# ColorOrgan_LEDs.net
KiCad netlist of a schematic drawn in Altium Designer
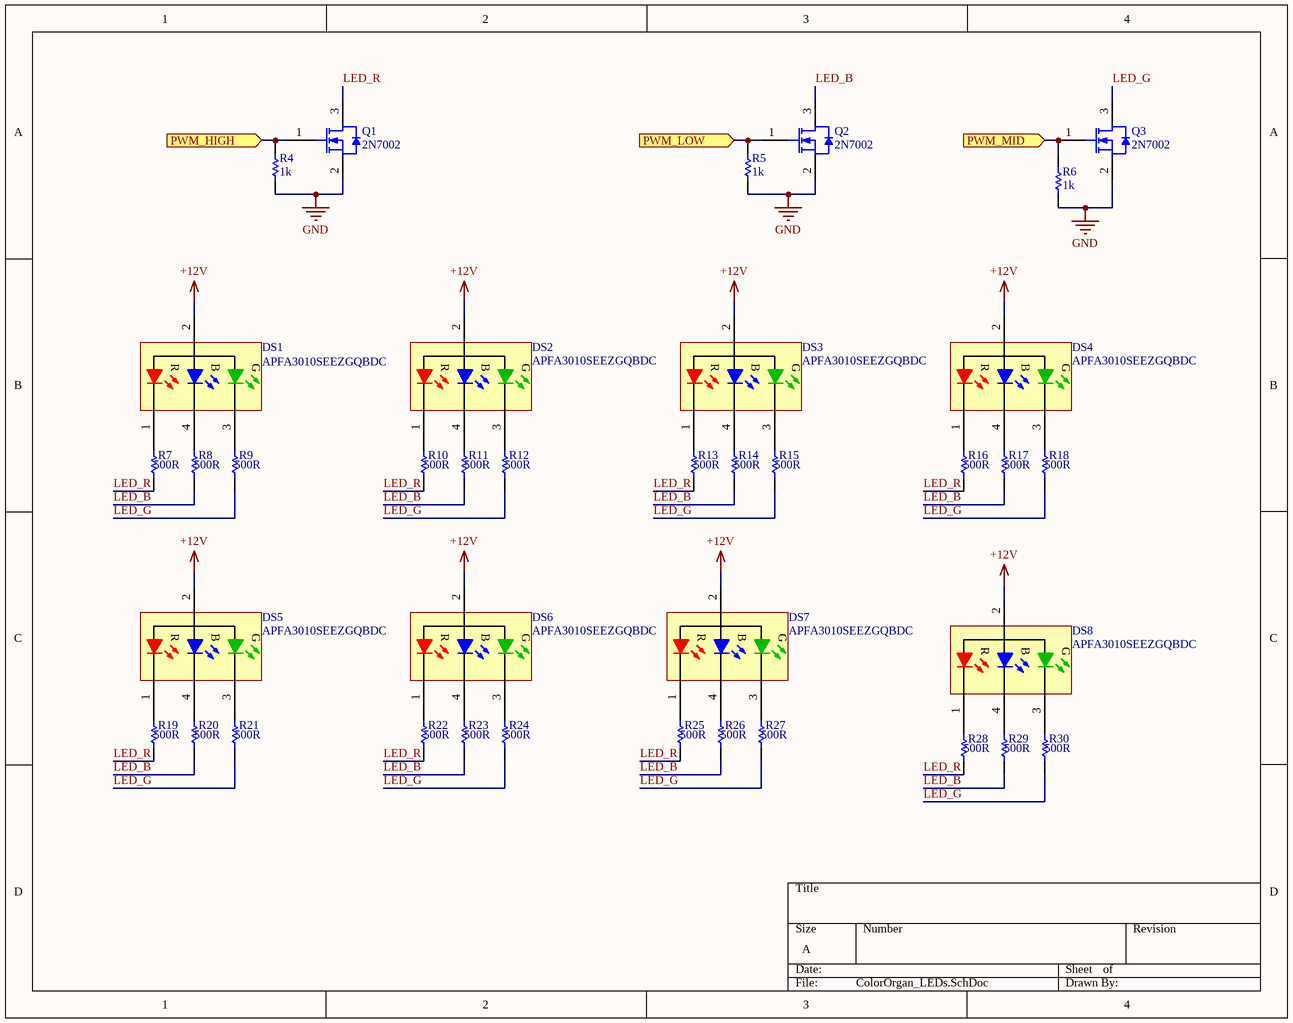
[diagram p0: ColorOrgan_LEDs.SchDoc]

(export (version "E")
  (design (tool "Eeschema 10.0.6"))
  (components
    (comp (ref "DS1")
      (value "APFA3010SEEZGQBDC")
      (footprint "KING-APFA3010SEEZGQBDC-4_V")
      (description "Right Angle SMD Chip LED Lamp, -40 to 85 degC, 4-Pin SMD, RoHS, Reel")
      (fields (field (name "MANUFACTURER") "Kingbright"))
      (libsource (lib "Altium Content Vault") (part "KING-LED_RGB_R1A2G3B4-4"))
    )
    (comp (ref "DS2")
      (value "APFA3010SEEZGQBDC")
      (footprint "KING-APFA3010SEEZGQBDC-4_V")
      (description "Right Angle SMD Chip LED Lamp, -40 to 85 degC, 4-Pin SMD, RoHS, Reel")
      (fields (field (name "MANUFACTURER") "Kingbright"))
      (libsource (lib "Altium Content Vault") (part "KING-LED_RGB_R1A2G3B4-4"))
    )
    (comp (ref "DS3")
      (value "APFA3010SEEZGQBDC")
      (footprint "KING-APFA3010SEEZGQBDC-4_V")
      (description "Right Angle SMD Chip LED Lamp, -40 to 85 degC, 4-Pin SMD, RoHS, Reel")
      (fields (field (name "MANUFACTURER") "Kingbright"))
      (libsource (lib "Altium Content Vault") (part "KING-LED_RGB_R1A2G3B4-4"))
    )
    (comp (ref "DS4")
      (value "APFA3010SEEZGQBDC")
      (footprint "KING-APFA3010SEEZGQBDC-4_V")
      (description "Right Angle SMD Chip LED Lamp, -40 to 85 degC, 4-Pin SMD, RoHS, Reel")
      (fields (field (name "MANUFACTURER") "Kingbright"))
      (libsource (lib "Altium Content Vault") (part "KING-LED_RGB_R1A2G3B4-4"))
    )
    (comp (ref "DS5")
      (value "APFA3010SEEZGQBDC")
      (footprint "KING-APFA3010SEEZGQBDC-4_V")
      (description "Right Angle SMD Chip LED Lamp, -40 to 85 degC, 4-Pin SMD, RoHS, Reel")
      (fields (field (name "MANUFACTURER") "Kingbright"))
      (libsource (lib "Altium Content Vault") (part "KING-LED_RGB_R1A2G3B4-4"))
    )
    (comp (ref "DS6")
      (value "APFA3010SEEZGQBDC")
      (footprint "KING-APFA3010SEEZGQBDC-4_V")
      (description "Right Angle SMD Chip LED Lamp, -40 to 85 degC, 4-Pin SMD, RoHS, Reel")
      (fields (field (name "MANUFACTURER") "Kingbright"))
      (libsource (lib "Altium Content Vault") (part "KING-LED_RGB_R1A2G3B4-4"))
    )
    (comp (ref "DS7")
      (value "APFA3010SEEZGQBDC")
      (footprint "KING-APFA3010SEEZGQBDC-4_V")
      (description "Right Angle SMD Chip LED Lamp, -40 to 85 degC, 4-Pin SMD, RoHS, Reel")
      (fields (field (name "MANUFACTURER") "Kingbright"))
      (libsource (lib "Altium Content Vault") (part "KING-LED_RGB_R1A2G3B4-4"))
    )
    (comp (ref "DS8")
      (value "APFA3010SEEZGQBDC")
      (footprint "KING-APFA3010SEEZGQBDC-4_V")
      (description "Right Angle SMD Chip LED Lamp, -40 to 85 degC, 4-Pin SMD, RoHS, Reel")
      (fields (field (name "MANUFACTURER") "Kingbright"))
      (libsource (lib "Altium Content Vault") (part "KING-LED_RGB_R1A2G3B4-4"))
    )
    (comp (ref "Q1")
      (value "2N7002")
      (footprint "STM-SOT-23-3_V")
      (description "N-channel 60 V, 1.8 Ohm, 0.35 A STripFET(TM) II Power MOSFET, SOT23")
      (fields (field (name "MANUFACTURER") "STMicroelectronics"))
      (libsource (lib "Altium Content Vault") (part "STM-NEMOS-G1S2D3-3"))
    )
    (comp (ref "Q2")
      (value "2N7002")
      (footprint "STM-SOT-23-3_V")
      (description "N-channel 60 V, 1.8 Ohm, 0.35 A STripFET(TM) II Power MOSFET, SOT23")
      (fields (field (name "MANUFACTURER") "STMicroelectronics"))
      (libsource (lib "Altium Content Vault") (part "STM-NEMOS-G1S2D3-3"))
    )
    (comp (ref "Q3")
      (value "2N7002")
      (footprint "STM-SOT-23-3_V")
      (description "N-channel 60 V, 1.8 Ohm, 0.35 A STripFET(TM) II Power MOSFET, SOT23")
      (fields (field (name "MANUFACTURER") "STMicroelectronics"))
      (libsource (lib "Altium Content Vault") (part "STM-NEMOS-G1S2D3-3"))
    )
    (comp (ref "R4")
      (value "1k")
      (footprint "RESC0805(2012)_L")
      (description "0805 (2012 Metric) Chip Resistor")
      (libsource (lib "Altium Content Vault") (part "RES_3"))
    )
    (comp (ref "R5")
      (value "1k")
      (footprint "RESC0805(2012)_L")
      (description "0805 (2012 Metric) Chip Resistor")
      (libsource (lib "Altium Content Vault") (part "RES_3"))
    )
    (comp (ref "R6")
      (value "1k")
      (footprint "RESC0805(2012)_L")
      (description "0805 (2012 Metric) Chip Resistor")
      (libsource (lib "Altium Content Vault") (part "RES_3"))
    )
    (comp (ref "R7")
      (value "500R")
      (footprint "RESC0805(2012)_L")
      (description "0805 (2012 Metric) Chip Resistor")
      (libsource (lib "Altium Content Vault") (part "RES_3"))
    )
    (comp (ref "R8")
      (value "500R")
      (footprint "RESC0805(2012)_L")
      (description "0805 (2012 Metric) Chip Resistor")
      (libsource (lib "Altium Content Vault") (part "RES_3"))
    )
    (comp (ref "R9")
      (value "500R")
      (footprint "RESC0805(2012)_L")
      (description "0805 (2012 Metric) Chip Resistor")
      (libsource (lib "Altium Content Vault") (part "RES_3"))
    )
    (comp (ref "R10")
      (value "500R")
      (footprint "RESC0805(2012)_L")
      (description "0805 (2012 Metric) Chip Resistor")
      (libsource (lib "Altium Content Vault") (part "RES_3"))
    )
    (comp (ref "R11")
      (value "500R")
      (footprint "RESC0805(2012)_L")
      (description "0805 (2012 Metric) Chip Resistor")
      (libsource (lib "Altium Content Vault") (part "RES_3"))
    )
    (comp (ref "R12")
      (value "500R")
      (footprint "RESC0805(2012)_L")
      (description "0805 (2012 Metric) Chip Resistor")
      (libsource (lib "Altium Content Vault") (part "RES_3"))
    )
    (comp (ref "R13")
      (value "500R")
      (footprint "RESC0805(2012)_L")
      (description "0805 (2012 Metric) Chip Resistor")
      (libsource (lib "Altium Content Vault") (part "RES_3"))
    )
    (comp (ref "R14")
      (value "500R")
      (footprint "RESC0805(2012)_L")
      (description "0805 (2012 Metric) Chip Resistor")
      (libsource (lib "Altium Content Vault") (part "RES_3"))
    )
    (comp (ref "R15")
      (value "500R")
      (footprint "RESC0805(2012)_L")
      (description "0805 (2012 Metric) Chip Resistor")
      (libsource (lib "Altium Content Vault") (part "RES_3"))
    )
    (comp (ref "R16")
      (value "500R")
      (footprint "RESC0805(2012)_L")
      (description "0805 (2012 Metric) Chip Resistor")
      (libsource (lib "Altium Content Vault") (part "RES_3"))
    )
    (comp (ref "R17")
      (value "500R")
      (footprint "RESC0805(2012)_L")
      (description "0805 (2012 Metric) Chip Resistor")
      (libsource (lib "Altium Content Vault") (part "RES_3"))
    )
    (comp (ref "R18")
      (value "500R")
      (footprint "RESC0805(2012)_L")
      (description "0805 (2012 Metric) Chip Resistor")
      (libsource (lib "Altium Content Vault") (part "RES_3"))
    )
    (comp (ref "R19")
      (value "500R")
      (footprint "RESC0805(2012)_L")
      (description "0805 (2012 Metric) Chip Resistor")
      (libsource (lib "Altium Content Vault") (part "RES_3"))
    )
    (comp (ref "R20")
      (value "500R")
      (footprint "RESC0805(2012)_L")
      (description "0805 (2012 Metric) Chip Resistor")
      (libsource (lib "Altium Content Vault") (part "RES_3"))
    )
    (comp (ref "R21")
      (value "500R")
      (footprint "RESC0805(2012)_L")
      (description "0805 (2012 Metric) Chip Resistor")
      (libsource (lib "Altium Content Vault") (part "RES_3"))
    )
    (comp (ref "R22")
      (value "500R")
      (footprint "RESC0805(2012)_L")
      (description "0805 (2012 Metric) Chip Resistor")
      (libsource (lib "Altium Content Vault") (part "RES_3"))
    )
    (comp (ref "R23")
      (value "500R")
      (footprint "RESC0805(2012)_L")
      (description "0805 (2012 Metric) Chip Resistor")
      (libsource (lib "Altium Content Vault") (part "RES_3"))
    )
    (comp (ref "R24")
      (value "500R")
      (footprint "RESC0805(2012)_L")
      (description "0805 (2012 Metric) Chip Resistor")
      (libsource (lib "Altium Content Vault") (part "RES_3"))
    )
    (comp (ref "R25")
      (value "500R")
      (footprint "RESC0805(2012)_L")
      (description "0805 (2012 Metric) Chip Resistor")
      (libsource (lib "Altium Content Vault") (part "RES_3"))
    )
    (comp (ref "R26")
      (value "500R")
      (footprint "RESC0805(2012)_L")
      (description "0805 (2012 Metric) Chip Resistor")
      (libsource (lib "Altium Content Vault") (part "RES_3"))
    )
    (comp (ref "R27")
      (value "500R")
      (footprint "RESC0805(2012)_L")
      (description "0805 (2012 Metric) Chip Resistor")
      (libsource (lib "Altium Content Vault") (part "RES_3"))
    )
    (comp (ref "R28")
      (value "500R")
      (footprint "RESC0805(2012)_L")
      (description "0805 (2012 Metric) Chip Resistor")
      (libsource (lib "Altium Content Vault") (part "RES_3"))
    )
    (comp (ref "R29")
      (value "500R")
      (footprint "RESC0805(2012)_L")
      (description "0805 (2012 Metric) Chip Resistor")
      (libsource (lib "Altium Content Vault") (part "RES_3"))
    )
    (comp (ref "R30")
      (value "500R")
      (footprint "RESC0805(2012)_L")
      (description "0805 (2012 Metric) Chip Resistor")
      (libsource (lib "Altium Content Vault") (part "RES_3"))
    )
  )
  (nets
    (net (code "1") (name "+12V") (class "Default")
      (node (ref "DS1") (pin "2") (pinfunction "A_2") (pintype "passive"))
      (node (ref "DS2") (pin "2") (pinfunction "A_2") (pintype "passive"))
      (node (ref "DS3") (pin "2") (pinfunction "A_2") (pintype "passive"))
      (node (ref "DS4") (pin "2") (pinfunction "A_2") (pintype "passive"))
      (node (ref "DS5") (pin "2") (pinfunction "A_2") (pintype "passive"))
      (node (ref "DS6") (pin "2") (pinfunction "A_2") (pintype "passive"))
      (node (ref "DS7") (pin "2") (pinfunction "A_2") (pintype "passive"))
      (node (ref "DS8") (pin "2") (pinfunction "A_2") (pintype "passive"))
    )
    (net (code "2") (name "/LED_B") (class "Default")
      (node (ref "Q2") (pin "3") (pinfunction "D_3") (pintype "passive"))
      (node (ref "R11") (pin "1") (pinfunction "1_1") (pintype "passive"))
      (node (ref "R14") (pin "1") (pinfunction "1_1") (pintype "passive"))
      (node (ref "R17") (pin "1") (pinfunction "1_1") (pintype "passive"))
      (node (ref "R20") (pin "1") (pinfunction "1_1") (pintype "passive"))
      (node (ref "R23") (pin "1") (pinfunction "1_1") (pintype "passive"))
      (node (ref "R26") (pin "1") (pinfunction "1_1") (pintype "passive"))
      (node (ref "R29") (pin "1") (pinfunction "1_1") (pintype "passive"))
      (node (ref "R8") (pin "1") (pinfunction "1_1") (pintype "passive"))
    )
    (net (code "3") (name "/LED_G") (class "Default")
      (node (ref "Q3") (pin "3") (pinfunction "D_3") (pintype "passive"))
      (node (ref "R12") (pin "1") (pinfunction "1_1") (pintype "passive"))
      (node (ref "R15") (pin "1") (pinfunction "1_1") (pintype "passive"))
      (node (ref "R18") (pin "1") (pinfunction "1_1") (pintype "passive"))
      (node (ref "R21") (pin "1") (pinfunction "1_1") (pintype "passive"))
      (node (ref "R24") (pin "1") (pinfunction "1_1") (pintype "passive"))
      (node (ref "R27") (pin "1") (pinfunction "1_1") (pintype "passive"))
      (node (ref "R30") (pin "1") (pinfunction "1_1") (pintype "passive"))
      (node (ref "R9") (pin "1") (pinfunction "1_1") (pintype "passive"))
    )
    (net (code "4") (name "/LED_R") (class "Default")
      (node (ref "Q1") (pin "3") (pinfunction "D_3") (pintype "passive"))
      (node (ref "R10") (pin "1") (pinfunction "1_1") (pintype "passive"))
      (node (ref "R13") (pin "1") (pinfunction "1_1") (pintype "passive"))
      (node (ref "R16") (pin "1") (pinfunction "1_1") (pintype "passive"))
      (node (ref "R19") (pin "1") (pinfunction "1_1") (pintype "passive"))
      (node (ref "R22") (pin "1") (pinfunction "1_1") (pintype "passive"))
      (node (ref "R25") (pin "1") (pinfunction "1_1") (pintype "passive"))
      (node (ref "R28") (pin "1") (pinfunction "1_1") (pintype "passive"))
      (node (ref "R7") (pin "1") (pinfunction "1_1") (pintype "passive"))
    )
    (net (code "5") (name "/PWM_HIGH") (class "Default")
      (node (ref "Q1") (pin "1") (pinfunction "G_1") (pintype "passive"))
      (node (ref "R4") (pin "2") (pinfunction "2_2") (pintype "passive"))
    )
    (net (code "6") (name "/PWM_LOW") (class "Default")
      (node (ref "Q2") (pin "1") (pinfunction "G_1") (pintype "passive"))
      (node (ref "R5") (pin "2") (pinfunction "2_2") (pintype "passive"))
    )
    (net (code "7") (name "/PWM_MID") (class "Default")
      (node (ref "Q3") (pin "1") (pinfunction "G_1") (pintype "passive"))
      (node (ref "R6") (pin "2") (pinfunction "2_2") (pintype "passive"))
    )
    (net (code "8") (name "GND") (class "Default")
      (node (ref "Q1") (pin "2") (pinfunction "S_2") (pintype "passive"))
      (node (ref "Q2") (pin "2") (pinfunction "S_2") (pintype "passive"))
      (node (ref "Q3") (pin "2") (pinfunction "S_2") (pintype "passive"))
      (node (ref "R4") (pin "1") (pinfunction "1_1") (pintype "passive"))
      (node (ref "R5") (pin "1") (pinfunction "1_1") (pintype "passive"))
      (node (ref "R6") (pin "1") (pinfunction "1_1") (pintype "passive"))
    )
    (net (code "9") (name "Net-(DS1-B)") (class "Default")
      (node (ref "DS1") (pin "4") (pinfunction "B_4") (pintype "passive"))
      (node (ref "R8") (pin "2") (pinfunction "2_2") (pintype "passive"))
    )
    (net (code "10") (name "Net-(DS1-G)") (class "Default")
      (node (ref "DS1") (pin "3") (pinfunction "G_3") (pintype "passive"))
      (node (ref "R9") (pin "2") (pinfunction "2_2") (pintype "passive"))
    )
    (net (code "11") (name "Net-(DS1-R)") (class "Default")
      (node (ref "DS1") (pin "1") (pinfunction "R_1") (pintype "passive"))
      (node (ref "R7") (pin "2") (pinfunction "2_2") (pintype "passive"))
    )
    (net (code "12") (name "Net-(DS2-B)") (class "Default")
      (node (ref "DS2") (pin "4") (pinfunction "B_4") (pintype "passive"))
      (node (ref "R11") (pin "2") (pinfunction "2_2") (pintype "passive"))
    )
    (net (code "13") (name "Net-(DS2-G)") (class "Default")
      (node (ref "DS2") (pin "3") (pinfunction "G_3") (pintype "passive"))
      (node (ref "R12") (pin "2") (pinfunction "2_2") (pintype "passive"))
    )
    (net (code "14") (name "Net-(DS2-R)") (class "Default")
      (node (ref "DS2") (pin "1") (pinfunction "R_1") (pintype "passive"))
      (node (ref "R10") (pin "2") (pinfunction "2_2") (pintype "passive"))
    )
    (net (code "15") (name "Net-(DS3-B)") (class "Default")
      (node (ref "DS3") (pin "4") (pinfunction "B_4") (pintype "passive"))
      (node (ref "R14") (pin "2") (pinfunction "2_2") (pintype "passive"))
    )
    (net (code "16") (name "Net-(DS3-G)") (class "Default")
      (node (ref "DS3") (pin "3") (pinfunction "G_3") (pintype "passive"))
      (node (ref "R15") (pin "2") (pinfunction "2_2") (pintype "passive"))
    )
    (net (code "17") (name "Net-(DS3-R)") (class "Default")
      (node (ref "DS3") (pin "1") (pinfunction "R_1") (pintype "passive"))
      (node (ref "R13") (pin "2") (pinfunction "2_2") (pintype "passive"))
    )
    (net (code "18") (name "Net-(DS4-B)") (class "Default")
      (node (ref "DS4") (pin "4") (pinfunction "B_4") (pintype "passive"))
      (node (ref "R17") (pin "2") (pinfunction "2_2") (pintype "passive"))
    )
    (net (code "19") (name "Net-(DS4-G)") (class "Default")
      (node (ref "DS4") (pin "3") (pinfunction "G_3") (pintype "passive"))
      (node (ref "R18") (pin "2") (pinfunction "2_2") (pintype "passive"))
    )
    (net (code "20") (name "Net-(DS4-R)") (class "Default")
      (node (ref "DS4") (pin "1") (pinfunction "R_1") (pintype "passive"))
      (node (ref "R16") (pin "2") (pinfunction "2_2") (pintype "passive"))
    )
    (net (code "21") (name "Net-(DS5-B)") (class "Default")
      (node (ref "DS5") (pin "4") (pinfunction "B_4") (pintype "passive"))
      (node (ref "R20") (pin "2") (pinfunction "2_2") (pintype "passive"))
    )
    (net (code "22") (name "Net-(DS5-G)") (class "Default")
      (node (ref "DS5") (pin "3") (pinfunction "G_3") (pintype "passive"))
      (node (ref "R21") (pin "2") (pinfunction "2_2") (pintype "passive"))
    )
    (net (code "23") (name "Net-(DS5-R)") (class "Default")
      (node (ref "DS5") (pin "1") (pinfunction "R_1") (pintype "passive"))
      (node (ref "R19") (pin "2") (pinfunction "2_2") (pintype "passive"))
    )
    (net (code "24") (name "Net-(DS6-B)") (class "Default")
      (node (ref "DS6") (pin "4") (pinfunction "B_4") (pintype "passive"))
      (node (ref "R23") (pin "2") (pinfunction "2_2") (pintype "passive"))
    )
    (net (code "25") (name "Net-(DS6-G)") (class "Default")
      (node (ref "DS6") (pin "3") (pinfunction "G_3") (pintype "passive"))
      (node (ref "R24") (pin "2") (pinfunction "2_2") (pintype "passive"))
    )
    (net (code "26") (name "Net-(DS6-R)") (class "Default")
      (node (ref "DS6") (pin "1") (pinfunction "R_1") (pintype "passive"))
      (node (ref "R22") (pin "2") (pinfunction "2_2") (pintype "passive"))
    )
    (net (code "27") (name "Net-(DS7-B)") (class "Default")
      (node (ref "DS7") (pin "4") (pinfunction "B_4") (pintype "passive"))
      (node (ref "R26") (pin "2") (pinfunction "2_2") (pintype "passive"))
    )
    (net (code "28") (name "Net-(DS7-G)") (class "Default")
      (node (ref "DS7") (pin "3") (pinfunction "G_3") (pintype "passive"))
      (node (ref "R27") (pin "2") (pinfunction "2_2") (pintype "passive"))
    )
    (net (code "29") (name "Net-(DS7-R)") (class "Default")
      (node (ref "DS7") (pin "1") (pinfunction "R_1") (pintype "passive"))
      (node (ref "R25") (pin "2") (pinfunction "2_2") (pintype "passive"))
    )
    (net (code "30") (name "Net-(DS8-B)") (class "Default")
      (node (ref "DS8") (pin "4") (pinfunction "B_4") (pintype "passive"))
      (node (ref "R29") (pin "2") (pinfunction "2_2") (pintype "passive"))
    )
    (net (code "31") (name "Net-(DS8-G)") (class "Default")
      (node (ref "DS8") (pin "3") (pinfunction "G_3") (pintype "passive"))
      (node (ref "R30") (pin "2") (pinfunction "2_2") (pintype "passive"))
    )
    (net (code "32") (name "Net-(DS8-R)") (class "Default")
      (node (ref "DS8") (pin "1") (pinfunction "R_1") (pintype "passive"))
      (node (ref "R28") (pin "2") (pinfunction "2_2") (pintype "passive"))
    )
  )
)
